# espAdapter.net
KiCad netlist of a schematic drawn in EAGLE
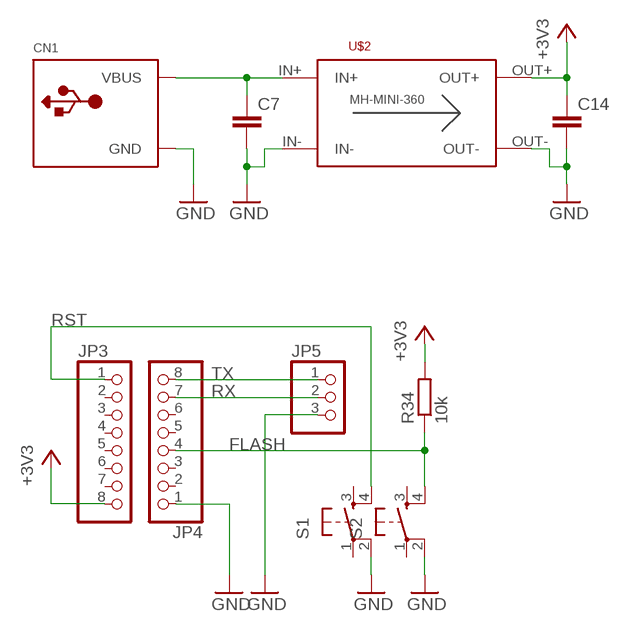
[diagram p0: schematic, sheet 1]

(export (version "E")
  (design (tool "Eeschema 10.0.6"))
  (components
    (comp (ref "C7")
      (value "C-EU025-025X050")
      (footprint "eagle-import:C025-025X050")
      (libsource (lib "eagle-import") (part "C-EU025-025X050"))
    )
    (comp (ref "C14")
      (value "C-EU025-025X050")
      (footprint "eagle-import:C025-025X050")
      (libsource (lib "eagle-import") (part "C-EU025-025X050"))
    )
    (comp (ref "CN1")
      (value "USBPWR-ONLY")
      (footprint "eagle-import:USB-MINIB-THM")
      (libsource (lib "eagle-import") (part "USBPWR-ONLY"))
    )
    (comp (ref "JP3")
      (value "PINHD-1X8")
      (footprint "eagle-import:1X08")
      (libsource (lib "eagle-import") (part "PINHD-1X8"))
    )
    (comp (ref "JP4")
      (value "PINHD-1X8")
      (footprint "eagle-import:1X08")
      (libsource (lib "eagle-import") (part "PINHD-1X8"))
    )
    (comp (ref "JP5")
      (value "PINHD-1X3")
      (footprint "eagle-import:1X03")
      (libsource (lib "eagle-import") (part "PINHD-1X3"))
    )
    (comp (ref "R34")
      (value "10k")
      (footprint "eagle-import:0204_7")
      (libsource (lib "eagle-import") (part "R-EU_0204/7"))
    )
    (comp (ref "S1")
      (value "TAC_SWITCHPTH")
      (footprint "eagle-import:TACTILE-PTH")
      (libsource (lib "eagle-import") (part "TAC_SWITCHPTH"))
    )
    (comp (ref "S2")
      (value "TAC_SWITCHPTH")
      (footprint "eagle-import:TACTILE-PTH")
      (libsource (lib "eagle-import") (part "TAC_SWITCHPTH"))
    )
    (comp (ref "U$2")
      (value "DC-DC_CONV_MINISTD")
      (footprint "eagle-import:DC-DC_CONV_MINI")
      (libsource (lib "eagle-import") (part "DC-DC_CONV_MINISTD"))
    )
  )
  (nets
    (net (code "1") (name "+3V3") (class "Default")
      (node (ref "C14") (pin "1") (pinfunction "1_1") (pintype "passive"))
      (node (ref "JP3") (pin "8") (pinfunction "8_8") (pintype "passive"))
      (node (ref "R34") (pin "2") (pinfunction "2_2") (pintype "passive"))
      (node (ref "U$2") (pin "OUT+") (pinfunction "OUT+_OUT+") (pintype "bidirectional"))
    )
    (net (code "2") (name "/FLASH") (class "Default")
      (node (ref "JP4") (pin "4") (pinfunction "4_4") (pintype "passive"))
      (node (ref "R34") (pin "1") (pinfunction "1_1") (pintype "passive"))
      (node (ref "S2") (pin "4") (pinfunction "4_4") (pintype "passive"))
    )
    (net (code "3") (name "/RST") (class "Default")
      (node (ref "JP3") (pin "1") (pinfunction "1_1") (pintype "passive"))
      (node (ref "S1") (pin "4") (pinfunction "4_4") (pintype "passive"))
    )
    (net (code "4") (name "/RX") (class "Default")
      (node (ref "JP4") (pin "7") (pinfunction "7_7") (pintype "passive"))
      (node (ref "JP5") (pin "2") (pinfunction "2_2") (pintype "passive"))
    )
    (net (code "5") (name "/TX") (class "Default")
      (node (ref "JP4") (pin "8") (pinfunction "8_8") (pintype "passive"))
      (node (ref "JP5") (pin "1") (pinfunction "1_1") (pintype "passive"))
    )
    (net (code "6") (name "GND") (class "Default")
      (node (ref "C14") (pin "2") (pinfunction "2_2") (pintype "passive"))
      (node (ref "C7") (pin "2") (pinfunction "2_2") (pintype "passive"))
      (node (ref "CN1") (pin "GND") (pinfunction "GND_GND") (pintype "power_in"))
      (node (ref "CN1") (pin "GND1") (pinfunction "GND_GND1") (pintype "power_in"))
      (node (ref "CN1") (pin "GND2") (pinfunction "GND_GND2") (pintype "power_in"))
      (node (ref "CN1") (pin "GND3") (pinfunction "GND_GND3") (pintype "power_in"))
      (node (ref "CN1") (pin "GND4") (pinfunction "GND_GND4") (pintype "power_in"))
      (node (ref "JP4") (pin "1") (pinfunction "1_1") (pintype "passive"))
      (node (ref "JP5") (pin "3") (pinfunction "3_3") (pintype "passive"))
      (node (ref "S1") (pin "2") (pinfunction "2_2") (pintype "passive"))
      (node (ref "S2") (pin "2") (pinfunction "2_2") (pintype "passive"))
      (node (ref "U$2") (pin "IN-") (pinfunction "IN-_IN-") (pintype "bidirectional"))
      (node (ref "U$2") (pin "OUT-") (pinfunction "OUT-_OUT-") (pintype "bidirectional"))
    )
    (net (code "7") (name "Net-(C7-Pad1)") (class "Default")
      (node (ref "C7") (pin "1") (pinfunction "1_1") (pintype "passive"))
      (node (ref "CN1") (pin "VBUS") (pinfunction "VBUS_VBUS") (pintype "power_in"))
      (node (ref "U$2") (pin "IN+") (pinfunction "IN+_IN+") (pintype "bidirectional"))
    )
    (net (code "8") (name "unconnected-(JP3-Pad2)") (class "Default")
      (node (ref "JP3") (pin "2") (pinfunction "2_2") (pintype "passive"))
    )
    (net (code "9") (name "unconnected-(JP3-Pad3)") (class "Default")
      (node (ref "JP3") (pin "3") (pinfunction "3_3") (pintype "passive"))
    )
    (net (code "10") (name "unconnected-(JP3-Pad4)") (class "Default")
      (node (ref "JP3") (pin "4") (pinfunction "4_4") (pintype "passive"))
    )
    (net (code "11") (name "unconnected-(JP3-Pad5)") (class "Default")
      (node (ref "JP3") (pin "5") (pinfunction "5_5") (pintype "passive"))
    )
    (net (code "12") (name "unconnected-(JP3-Pad6)") (class "Default")
      (node (ref "JP3") (pin "6") (pinfunction "6_6") (pintype "passive"))
    )
    (net (code "13") (name "unconnected-(JP3-Pad7)") (class "Default")
      (node (ref "JP3") (pin "7") (pinfunction "7_7") (pintype "passive"))
    )
    (net (code "14") (name "unconnected-(JP4-Pad2)") (class "Default")
      (node (ref "JP4") (pin "2") (pinfunction "2_2") (pintype "passive"))
    )
    (net (code "15") (name "unconnected-(JP4-Pad3)") (class "Default")
      (node (ref "JP4") (pin "3") (pinfunction "3_3") (pintype "passive"))
    )
    (net (code "16") (name "unconnected-(JP4-Pad5)") (class "Default")
      (node (ref "JP4") (pin "5") (pinfunction "5_5") (pintype "passive"))
    )
    (net (code "17") (name "unconnected-(JP4-Pad6)") (class "Default")
      (node (ref "JP4") (pin "6") (pinfunction "6_6") (pintype "passive"))
    )
    (net (code "18") (name "unconnected-(S1-Pad1)") (class "Default")
      (node (ref "S1") (pin "1") (pinfunction "1_1") (pintype "passive"))
    )
    (net (code "19") (name "unconnected-(S1-Pad3)") (class "Default")
      (node (ref "S1") (pin "3") (pinfunction "3_3") (pintype "passive"))
    )
    (net (code "20") (name "unconnected-(S2-Pad1)") (class "Default")
      (node (ref "S2") (pin "1") (pinfunction "1_1") (pintype "passive"))
    )
    (net (code "21") (name "unconnected-(S2-Pad3)") (class "Default")
      (node (ref "S2") (pin "3") (pinfunction "3_3") (pintype "passive"))
    )
  )
)
